# Microcontroller.net
KiCad netlist of a schematic drawn in Altium Designer
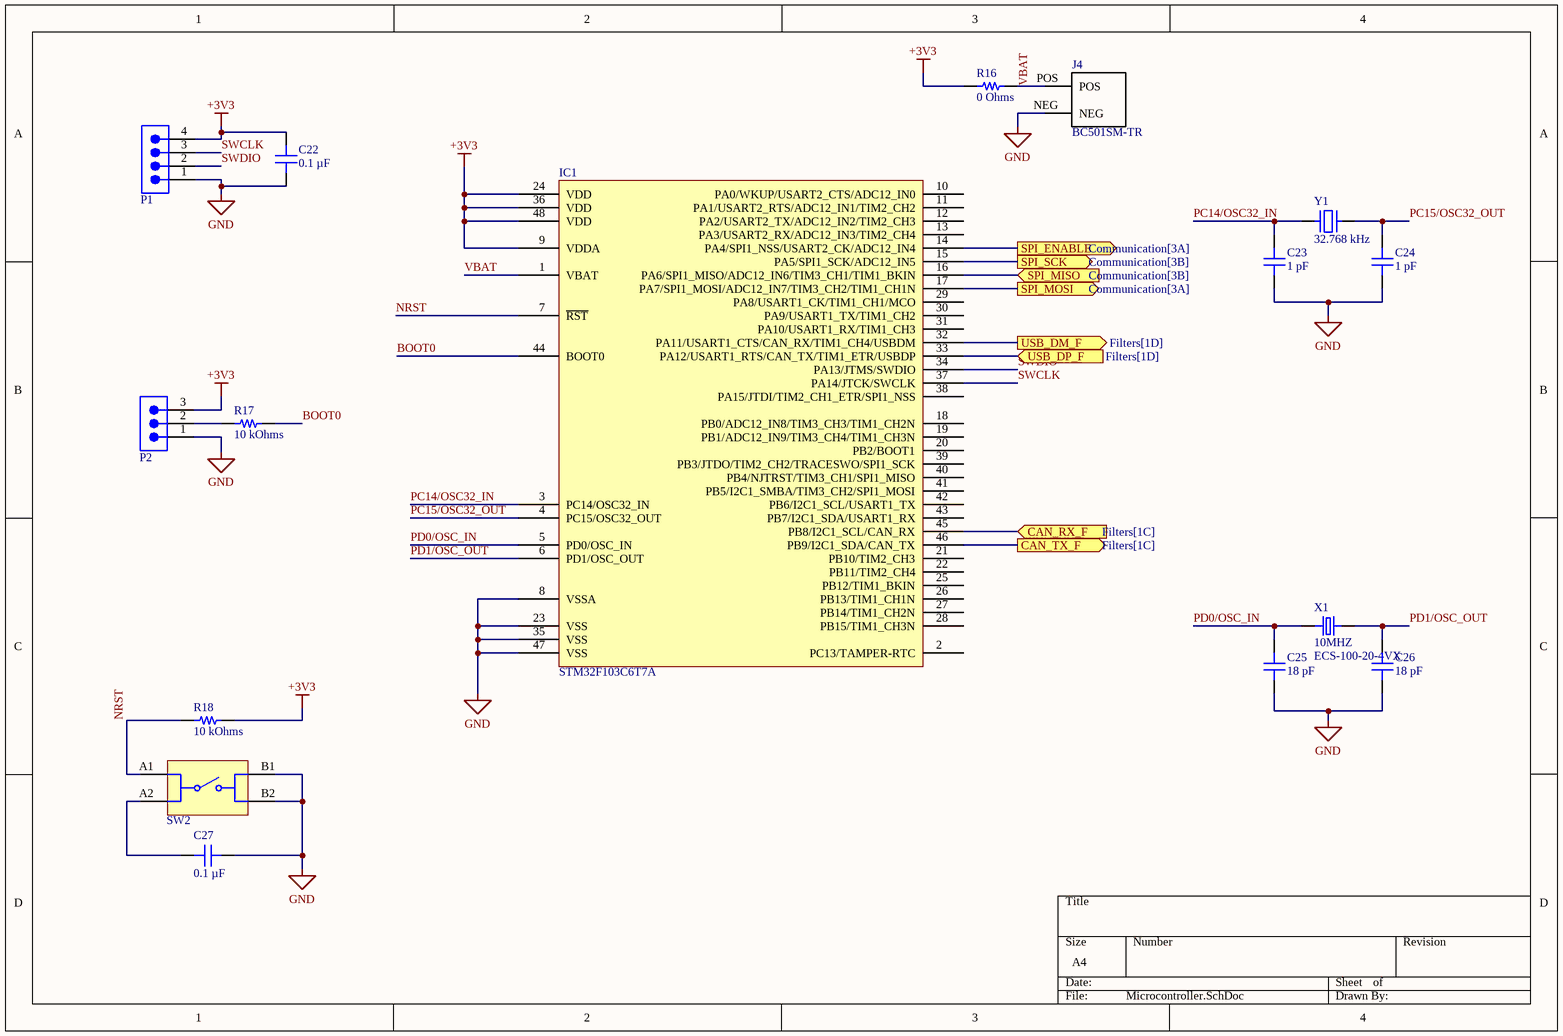
[diagram p0: Microcontroller.SchDoc]

(export (version "E")
  (design (tool "Eeschema 10.0.6"))
  (components
    (comp (ref "C22")
      (value "0.1 µF")
      (footprint "CAP 0805_2012")
      (description "CAP CER 0.1UF 50V X7R 0805")
      (fields (field (name "PART NUMBER") "CC0805MRX7R9BB104") (field (name "MANUFACTURER") "Yageo"))
      (libsource (lib "Celestial Altium Library - altium_library (2)") (part "Capacitor"))
    )
    (comp (ref "C23")
      (value "1 pF")
      (footprint "CAP 0805_2012")
      (description "CAP CER 1PF 50V C0G/NPO 0805")
      (fields (field (name "PART NUMBER") "CC0805CRNPO9BN1R0") (field (name "MANUFACTURER") "Yageo"))
      (libsource (lib "Celestial Altium Library - altium_library (2)") (part "Capacitor"))
    )
    (comp (ref "C24")
      (value "1 pF")
      (footprint "CAP 0805_2012")
      (description "CAP CER 1PF 50V C0G/NPO 0805")
      (fields (field (name "PART NUMBER") "CC0805CRNPO9BN1R0") (field (name "MANUFACTURER") "Yageo"))
      (libsource (lib "Celestial Altium Library - altium_library (2)") (part "Capacitor"))
    )
    (comp (ref "C25")
      (value "18 pF")
      (footprint "CAP 0805_2012")
      (description "CAP CER 18PF 25V C0G/NP0 0805")
      (fields
        (field (name "PART NUMBER") "VJ0805A180JXXCW1BC")
        (field (name "MANUFACTURER") "Vishay Vitramon")
      )
      (libsource (lib "Celestial Altium Library - altium_library (2)") (part "Capacitor"))
    )
    (comp (ref "C26")
      (value "18 pF")
      (footprint "CAP 0805_2012")
      (description "CAP CER 18PF 25V C0G/NP0 0805")
      (fields
        (field (name "PART NUMBER") "VJ0805A180JXXCW1BC")
        (field (name "MANUFACTURER") "Vishay Vitramon")
      )
      (libsource (lib "Celestial Altium Library - altium_library (2)") (part "Capacitor"))
    )
    (comp (ref "C27")
      (value "0.1 µF")
      (footprint "CAP 0805_2012")
      (description "CAP CER 0.1UF 50V X7R 0805")
      (fields (field (name "PART NUMBER") "CC0805MRX7R9BB104") (field (name "MANUFACTURER") "Yageo"))
      (libsource (lib "Celestial Altium Library - altium_library (2)") (part "Capacitor"))
    )
    (comp (ref "IC1")
      (value "STM32F103C6T7A")
      (footprint "ST LQFP-48 7X7MM")
      (description "IC MCU 32BIT 32KB FLASH 48LQFP")
      (fields (field (name "MANUFACTURER") "STMicroelectronics"))
      (libsource (lib "Celestial Altium Library - altium_library (2)") (part "ST STM32F103 48PIN"))
    )
    (comp (ref "J4")
      (value "BC501SM-TR")
      (footprint "*MPD_BC501SM-TR_BC501SM-TR(Primary) - duplicate")
      (description "Holder Coin Cell For Cr1220 Smd")
      (fields (field (name "DIGI-KEY_PART_NUMBER") "BC501SM-TRCT-ND") (field (name "MF") "MPD _Memory"))
      (libsource (lib "Schlib1") (part "BC501SM-TR"))
    )
    (comp (ref "P1")
      (value "61900411121")
      (footprint "61900411121")
      (description "WR-WTB THT Male Vertical Locking Header, pitch 2.54mm, 4pins")
      (fields (field (name "MANUFACTURER") "Wurth Elektronik"))
      (libsource (lib "WE - Electromechanical Components") (part "Header_Male_1R_04P"))
    )
    (comp (ref "P2")
      (value "61900311121")
      (footprint "61900311121")
      (description "WR-WTB THT Male Vertical Locking Header, pitch 2.54mm, 3pins")
      (fields (field (name "MANUFACTURER") "Wurth Elektronik"))
      (libsource (lib "WE - Electromechanical Components") (part "Header_Male_1R_03P"))
    )
    (comp (ref "R16")
      (value "0 Ohms")
      (footprint "RES 0805_2012")
      (description "RES 0 OHM JUMPER 0805")
      (fields (field (name "PART NUMBER") "5107") (field (name "MANUFACTURER") "Keystone Electronics"))
      (libsource (lib "Celestial Altium Library - altium_library (2)") (part "Resistor"))
    )
    (comp (ref "R17")
      (value "10 kOhms")
      (footprint "RES 0805_2012")
      (description "RES SMD 10K OHM 0.1% 1/4W 0805")
      (fields
        (field (name "PART NUMBER") "2176093-5")
        (field (name "MANUFACTURER") "TE Connectivity Passive Product")
      )
      (libsource (lib "Celestial Altium Library - altium_library (2)") (part "Resistor"))
    )
    (comp (ref "R18")
      (value "10 kOhms")
      (footprint "RES 0805_2012")
      (description "RES SMD 10K OHM 0.1% 1/4W 0805")
      (fields
        (field (name "PART NUMBER") "2176093-5")
        (field (name "MANUFACTURER") "TE Connectivity Passive Product")
      )
      (libsource (lib "Celestial Altium Library - altium_library (2)") (part "Resistor"))
    )
    (comp (ref "SW2")
      (value "430152043826")
      (footprint "WS-TASV_L6W6H4.3_4301x20438x6")
      (description "WS-TASV SMT Tact Switch, L6 x W6 x H4.3mm, 260g, SPST-NO, 12V, 50mA")
      (fields (field (name "MANUFACTURER") "Wurth Elektronik"))
      (libsource (lib "WE - Electromechanical Components") (part "SPST-NO_4P"))
    )
    (comp (ref "X1")
      (value "ECS-100-20-4VX")
      (footprint "XTAL_ECS-100-20-4VX")
      (description "ECS-100-20-4VX 10MHz")
      (fields
        (field (name "MANUFACTURER") "ESC INC")
        (field (name "FREQUENCY") "10MHZ")
        (field (name "SUPPLIER PART NUMBER 1") "ECS-100-20-4VX")
      )
      (libsource (lib "Schlib1") (part "ECS-100-20-4VX"))
    )
    (comp (ref "Y1")
      (value "32.768 kHz")
      (footprint "ABRACON ABS07")
      (description "CRYSTAL 32.7680KHZ 6PF SMD")
      (fields (field (name "PART NUMBER") "ABS07-32.768KHZ-6-T") (field (name "MANUFACTURER") "Abracon LLC"))
      (libsource (lib "Celestial Altium Library - altium_library (2)") (part "Abracon Crystal ABS07"))
    )
  )
  (nets
    (net (code "1") (name "+3V3") (class "Default")
      (node (ref "C22") (pin "1") (pinfunction "1_1") (pintype "passive"))
      (node (ref "IC1") (pin "24") (pinfunction "VDD_24") (pintype "passive"))
      (node (ref "IC1") (pin "36") (pinfunction "VDD_36") (pintype "passive"))
      (node (ref "IC1") (pin "48") (pinfunction "VDD_48") (pintype "passive"))
      (node (ref "IC1") (pin "9") (pinfunction "VDDA_9") (pintype "passive"))
      (node (ref "P1") (pin "4") (pinfunction "4_4") (pintype "passive"))
      (node (ref "P2") (pin "3") (pinfunction "3_3") (pintype "passive"))
      (node (ref "R16") (pin "1") (pinfunction "1_1") (pintype "passive"))
      (node (ref "R18") (pin "2") (pinfunction "2_2") (pintype "passive"))
    )
    (net (code "2") (name "/BOOT0") (class "Default")
      (node (ref "IC1") (pin "44") (pinfunction "BOOT0_44") (pintype "passive"))
      (node (ref "R17") (pin "2") (pinfunction "2_2") (pintype "passive"))
    )
    (net (code "3") (name "/CAN_RX_F") (class "Default")
      (node (ref "IC1") (pin "45") (pinfunction "PB8/I2C1_SCL/CAN_RX_45") (pintype "passive"))
    )
    (net (code "4") (name "/CAN_TX_F") (class "Default")
      (node (ref "IC1") (pin "46") (pinfunction "PB9/I2C1_SDA/CAN_TX_46") (pintype "passive"))
    )
    (net (code "5") (name "/NRST") (class "Default")
      (node (ref "IC1") (pin "7") (pinfunction "~{RST}_7") (pintype "passive"))
      (node (ref "R18") (pin "1") (pinfunction "1_1") (pintype "passive"))
      (node (ref "SW2") (pin "A1") (pinfunction "A1_A1") (pintype "passive"))
    )
    (net (code "6") (name "/PC14{slash}OSC32_IN") (class "Default")
      (node (ref "C23") (pin "2") (pinfunction "2_2") (pintype "passive"))
      (node (ref "IC1") (pin "3") (pinfunction "PC14/OSC32_IN_3") (pintype "passive"))
      (node (ref "Y1") (pin "1") (pinfunction "1_1") (pintype "passive"))
    )
    (net (code "7") (name "/PC15{slash}OSC32_OUT") (class "Default")
      (node (ref "C24") (pin "2") (pinfunction "2_2") (pintype "passive"))
      (node (ref "IC1") (pin "4") (pinfunction "PC15/OSC32_OUT_4") (pintype "passive"))
      (node (ref "Y1") (pin "2") (pinfunction "2_2") (pintype "passive"))
    )
    (net (code "8") (name "/PD0{slash}OSC_IN") (class "Default")
      (node (ref "C25") (pin "2") (pinfunction "2_2") (pintype "passive"))
      (node (ref "IC1") (pin "5") (pinfunction "PD0/OSC_IN_5") (pintype "passive"))
      (node (ref "X1") (pin "1") (pinfunction "1_1") (pintype "passive"))
    )
    (net (code "9") (name "/PD1{slash}OSC_OUT") (class "Default")
      (node (ref "C26") (pin "2") (pinfunction "2_2") (pintype "passive"))
      (node (ref "IC1") (pin "6") (pinfunction "PD1/OSC_OUT_6") (pintype "passive"))
      (node (ref "X1") (pin "2") (pinfunction "2_2") (pintype "passive"))
    )
    (net (code "10") (name "/SPI_ENABLE") (class "Default")
      (node (ref "IC1") (pin "14") (pinfunction "PA4/SPI1_NSS/USART2_CK/ADC12_IN4_14") (pintype "passive"))
    )
    (net (code "11") (name "/SPI_MISO") (class "Default")
      (node (ref "IC1") (pin "16") (pinfunction "PA6/SPI1_MISO/ADC12_IN6/TIM3_CH1/TIM1_BKIN_16") (pintype "passive"))
    )
    (net (code "12") (name "/SPI_MOSI") (class "Default")
      (node (ref "IC1") (pin "17") (pinfunction "PA7/SPI1_MOSI/ADC12_IN7/TIM3_CH2/TIM1_CH1N_17") (pintype "passive"))
    )
    (net (code "13") (name "/SPI_SCK") (class "Default")
      (node (ref "IC1") (pin "15") (pinfunction "PA5/SPI1_SCK/ADC12_IN5_15") (pintype "passive"))
    )
    (net (code "14") (name "/SWCLK") (class "Default")
      (node (ref "IC1") (pin "37") (pinfunction "PA14/JTCK/SWCLK_37") (pintype "passive"))
      (node (ref "P1") (pin "3") (pinfunction "3_3") (pintype "passive"))
    )
    (net (code "15") (name "/SWDIO") (class "Default")
      (node (ref "IC1") (pin "34") (pinfunction "PA13/JTMS/SWDIO_34") (pintype "passive"))
      (node (ref "P1") (pin "2") (pinfunction "2_2") (pintype "passive"))
    )
    (net (code "16") (name "/USB_DM_F") (class "Default")
      (node (ref "IC1") (pin "32") (pinfunction "PA11/USART1_CTS/CAN_RX/TIM1_CH4/USBDM_32") (pintype "passive"))
    )
    (net (code "17") (name "/USB_DP_F") (class "Default")
      (node (ref "IC1") (pin "33") (pinfunction "PA12/USART1_RTS/CAN_TX/TIM1_ETR/USBDP_33") (pintype "passive"))
    )
    (net (code "18") (name "/VBAT") (class "Default")
      (node (ref "IC1") (pin "1") (pinfunction "VBAT_1") (pintype "passive"))
      (node (ref "J4") (pin "POS") (pinfunction "POS_POS") (pintype "passive"))
      (node (ref "R16") (pin "2") (pinfunction "2_2") (pintype "passive"))
    )
    (net (code "19") (name "GND") (class "Default")
      (node (ref "C22") (pin "2") (pinfunction "2_2") (pintype "passive"))
      (node (ref "C23") (pin "1") (pinfunction "1_1") (pintype "passive"))
      (node (ref "C24") (pin "1") (pinfunction "1_1") (pintype "passive"))
      (node (ref "C25") (pin "1") (pinfunction "1_1") (pintype "passive"))
      (node (ref "C26") (pin "1") (pinfunction "1_1") (pintype "passive"))
      (node (ref "C27") (pin "1") (pinfunction "1_1") (pintype "passive"))
      (node (ref "IC1") (pin "23") (pinfunction "VSS_23") (pintype "passive"))
      (node (ref "IC1") (pin "35") (pinfunction "VSS_35") (pintype "passive"))
      (node (ref "IC1") (pin "47") (pinfunction "VSS_47") (pintype "passive"))
      (node (ref "IC1") (pin "8") (pinfunction "VSSA_8") (pintype "passive"))
      (node (ref "J4") (pin "NEG") (pinfunction "NEG_NEG") (pintype "passive"))
      (node (ref "P1") (pin "1") (pinfunction "1_1") (pintype "passive"))
      (node (ref "P2") (pin "1") (pinfunction "1_1") (pintype "passive"))
      (node (ref "SW2") (pin "B1") (pinfunction "B1_B1") (pintype "passive"))
      (node (ref "SW2") (pin "B2") (pinfunction "B2_B2") (pintype "passive"))
    )
    (net (code "20") (name "Net-(C27-Pad2)") (class "Default")
      (node (ref "C27") (pin "2") (pinfunction "2_2") (pintype "passive"))
      (node (ref "SW2") (pin "A2") (pinfunction "A2_A2") (pintype "passive"))
    )
    (net (code "21") (name "Net-(P2-Pad2)") (class "Default")
      (node (ref "P2") (pin "2") (pinfunction "2_2") (pintype "passive"))
      (node (ref "R17") (pin "1") (pinfunction "1_1") (pintype "passive"))
    )
    (net (code "22") (name "unconnected-(IC1-PA0{slash}WKUP{slash}USART2_CTS{slash}ADC12_IN0-Pad10)") (class "Default")
      (node (ref "IC1") (pin "10") (pinfunction "PA0/WKUP/USART2_CTS/ADC12_IN0_10") (pintype "passive"))
    )
    (net (code "23") (name "unconnected-(IC1-PA1{slash}USART2_RTS{slash}ADC12_IN1{slash}TIM2_CH2-Pad11)") (class "Default")
      (node (ref "IC1") (pin "11") (pinfunction "PA1/USART2_RTS/ADC12_IN1/TIM2_CH2_11") (pintype "passive"))
    )
    (net (code "24") (name "unconnected-(IC1-PA2{slash}USART2_TX{slash}ADC12_IN2{slash}TIM2_CH3-Pad12)") (class "Default")
      (node (ref "IC1") (pin "12") (pinfunction "PA2/USART2_TX/ADC12_IN2/TIM2_CH3_12") (pintype "passive"))
    )
    (net (code "25") (name "unconnected-(IC1-PA3{slash}USART2_RX{slash}ADC12_IN3{slash}TIM2_CH4-Pad13)") (class "Default")
      (node (ref "IC1") (pin "13") (pinfunction "PA3/USART2_RX/ADC12_IN3/TIM2_CH4_13") (pintype "passive"))
    )
    (net (code "26") (name "unconnected-(IC1-PA8{slash}USART1_CK{slash}TIM1_CH1{slash}MCO-Pad29)") (class "Default")
      (node (ref "IC1") (pin "29") (pinfunction "PA8/USART1_CK/TIM1_CH1/MCO_29") (pintype "passive"))
    )
    (net (code "27") (name "unconnected-(IC1-PA9{slash}USART1_TX{slash}TIM1_CH2-Pad30)") (class "Default")
      (node (ref "IC1") (pin "30") (pinfunction "PA9/USART1_TX/TIM1_CH2_30") (pintype "passive"))
    )
    (net (code "28") (name "unconnected-(IC1-PA10{slash}USART1_RX{slash}TIM1_CH3-Pad31)") (class "Default")
      (node (ref "IC1") (pin "31") (pinfunction "PA10/USART1_RX/TIM1_CH3_31") (pintype "passive"))
    )
    (net (code "29") (name "unconnected-(IC1-PA15{slash}JTDI{slash}TIM2_CH1_ETR{slash}SPI1_NSS-Pad38)") (class "Default")
      (node (ref "IC1") (pin "38") (pinfunction "PA15/JTDI/TIM2_CH1_ETR/SPI1_NSS_38") (pintype "passive"))
    )
    (net (code "30") (name "unconnected-(IC1-PB0{slash}ADC12_IN8{slash}TIM3_CH3{slash}TIM1_CH2N-Pad18)") (class "Default")
      (node (ref "IC1") (pin "18") (pinfunction "PB0/ADC12_IN8/TIM3_CH3/TIM1_CH2N_18") (pintype "passive"))
    )
    (net (code "31") (name "unconnected-(IC1-PB1{slash}ADC12_IN9{slash}TIM3_CH4{slash}TIM1_CH3N-Pad19)") (class "Default")
      (node (ref "IC1") (pin "19") (pinfunction "PB1/ADC12_IN9/TIM3_CH4/TIM1_CH3N_19") (pintype "passive"))
    )
    (net (code "32") (name "unconnected-(IC1-PB2{slash}BOOT1-Pad20)") (class "Default")
      (node (ref "IC1") (pin "20") (pinfunction "PB2/BOOT1_20") (pintype "passive"))
    )
    (net (code "33") (name "unconnected-(IC1-PB3{slash}JTDO{slash}TIM2_CH2{slash}TRACESWO{slash}SPI1_SCK-Pad39)") (class "Default")
      (node (ref "IC1") (pin "39") (pinfunction "PB3/JTDO/TIM2_CH2/TRACESWO/SPI1_SCK_39") (pintype "passive"))
    )
    (net (code "34") (name "unconnected-(IC1-PB4{slash}NJTRST{slash}TIM3_CH1{slash}SPI1_MISO-Pad40)") (class "Default")
      (node (ref "IC1") (pin "40") (pinfunction "PB4/NJTRST/TIM3_CH1/SPI1_MISO_40") (pintype "passive"))
    )
    (net (code "35") (name "unconnected-(IC1-PB5{slash}I2C1_SMBA{slash}TIM3_CH2{slash}SPI1_MOSI-Pad41)") (class "Default")
      (node (ref "IC1") (pin "41") (pinfunction "PB5/I2C1_SMBA/TIM3_CH2/SPI1_MOSI_41") (pintype "passive"))
    )
    (net (code "36") (name "unconnected-(IC1-PB6{slash}I2C1_SCL{slash}USART1_TX-Pad42)") (class "Default")
      (node (ref "IC1") (pin "42") (pinfunction "PB6/I2C1_SCL/USART1_TX_42") (pintype "passive"))
    )
    (net (code "37") (name "unconnected-(IC1-PB7{slash}I2C1_SDA{slash}USART1_RX-Pad43)") (class "Default")
      (node (ref "IC1") (pin "43") (pinfunction "PB7/I2C1_SDA/USART1_RX_43") (pintype "passive"))
    )
    (net (code "38") (name "unconnected-(IC1-PB10{slash}TIM2_CH3-Pad21)") (class "Default")
      (node (ref "IC1") (pin "21") (pinfunction "PB10/TIM2_CH3_21") (pintype "passive"))
    )
    (net (code "39") (name "unconnected-(IC1-PB11{slash}TIM2_CH4-Pad22)") (class "Default")
      (node (ref "IC1") (pin "22") (pinfunction "PB11/TIM2_CH4_22") (pintype "passive"))
    )
    (net (code "40") (name "unconnected-(IC1-PB12{slash}TIM1_BKIN-Pad25)") (class "Default")
      (node (ref "IC1") (pin "25") (pinfunction "PB12/TIM1_BKIN_25") (pintype "passive"))
    )
    (net (code "41") (name "unconnected-(IC1-PB13{slash}TIM1_CH1N-Pad26)") (class "Default")
      (node (ref "IC1") (pin "26") (pinfunction "PB13/TIM1_CH1N_26") (pintype "passive"))
    )
    (net (code "42") (name "unconnected-(IC1-PB14{slash}TIM1_CH2N-Pad27)") (class "Default")
      (node (ref "IC1") (pin "27") (pinfunction "PB14/TIM1_CH2N_27") (pintype "passive"))
    )
    (net (code "43") (name "unconnected-(IC1-PB15{slash}TIM1_CH3N-Pad28)") (class "Default")
      (node (ref "IC1") (pin "28") (pinfunction "PB15/TIM1_CH3N_28") (pintype "passive"))
    )
    (net (code "44") (name "unconnected-(IC1-PC13{slash}TAMPER-RTC-Pad2)") (class "Default")
      (node (ref "IC1") (pin "2") (pinfunction "PC13/TAMPER-RTC_2") (pintype "passive"))
    )
  )
)
